# Brain1portB.net
KiCad netlist of a schematic drawn in EAGLE
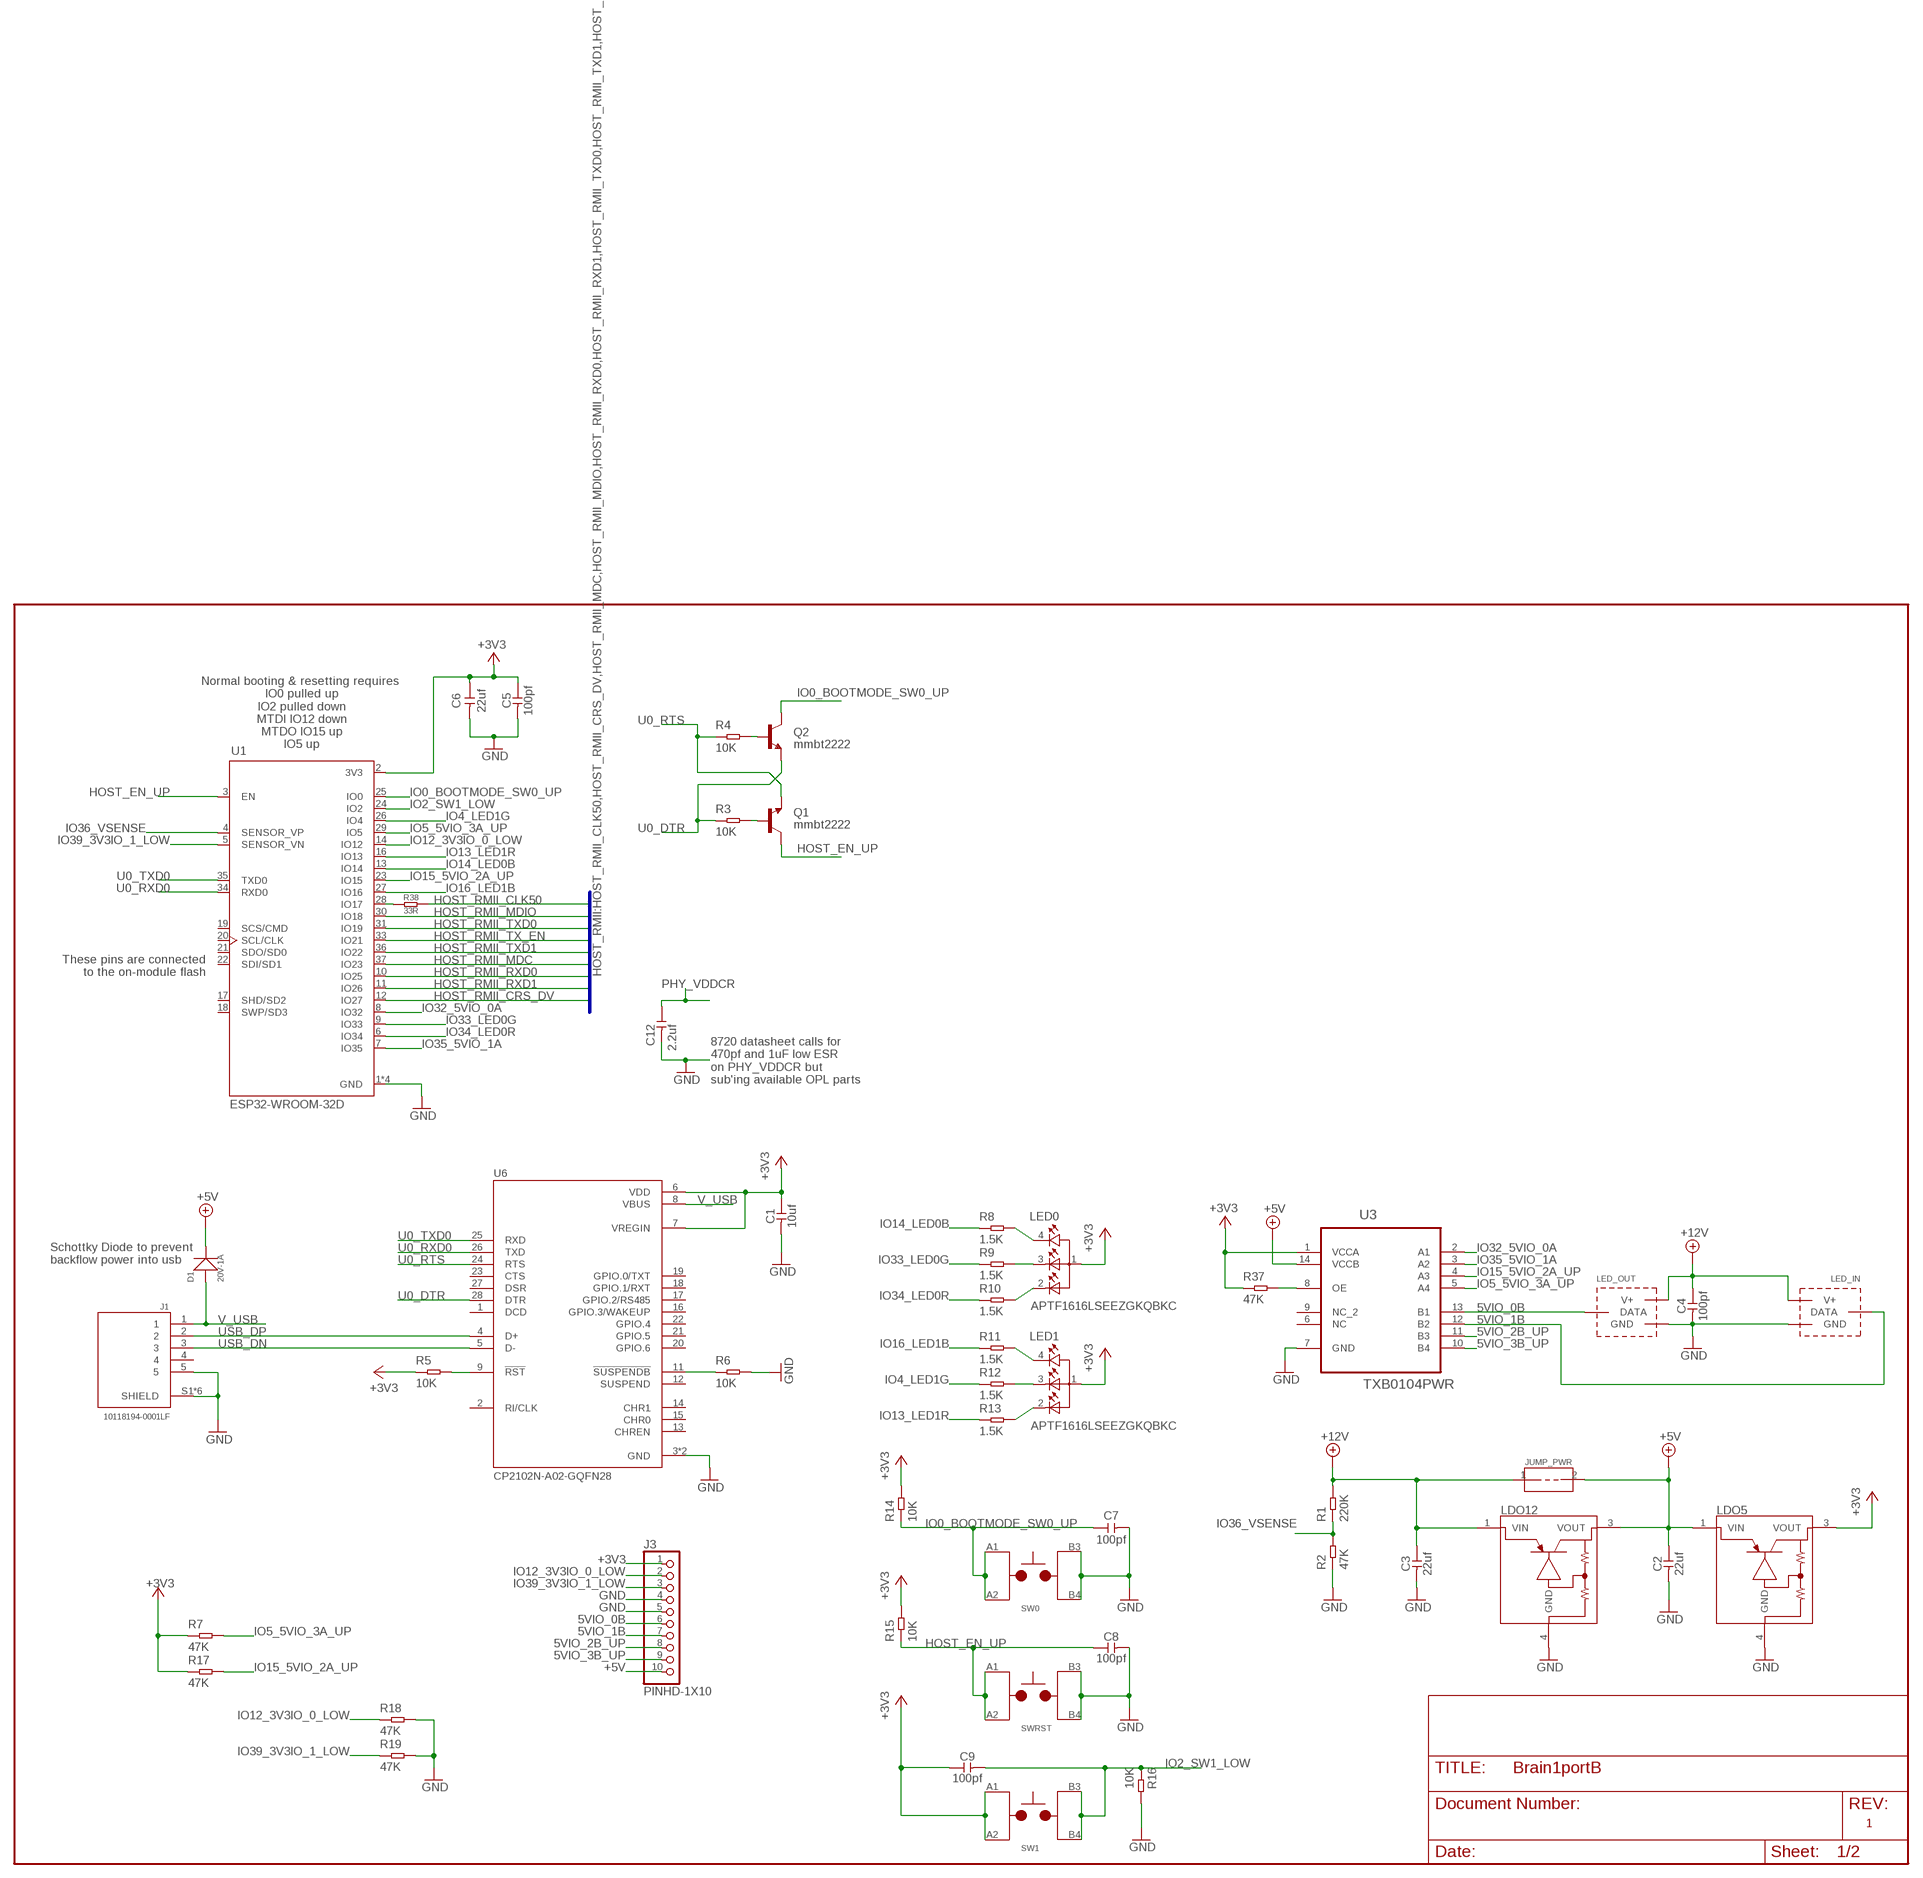
[diagram p0: schematic, sheet 1]
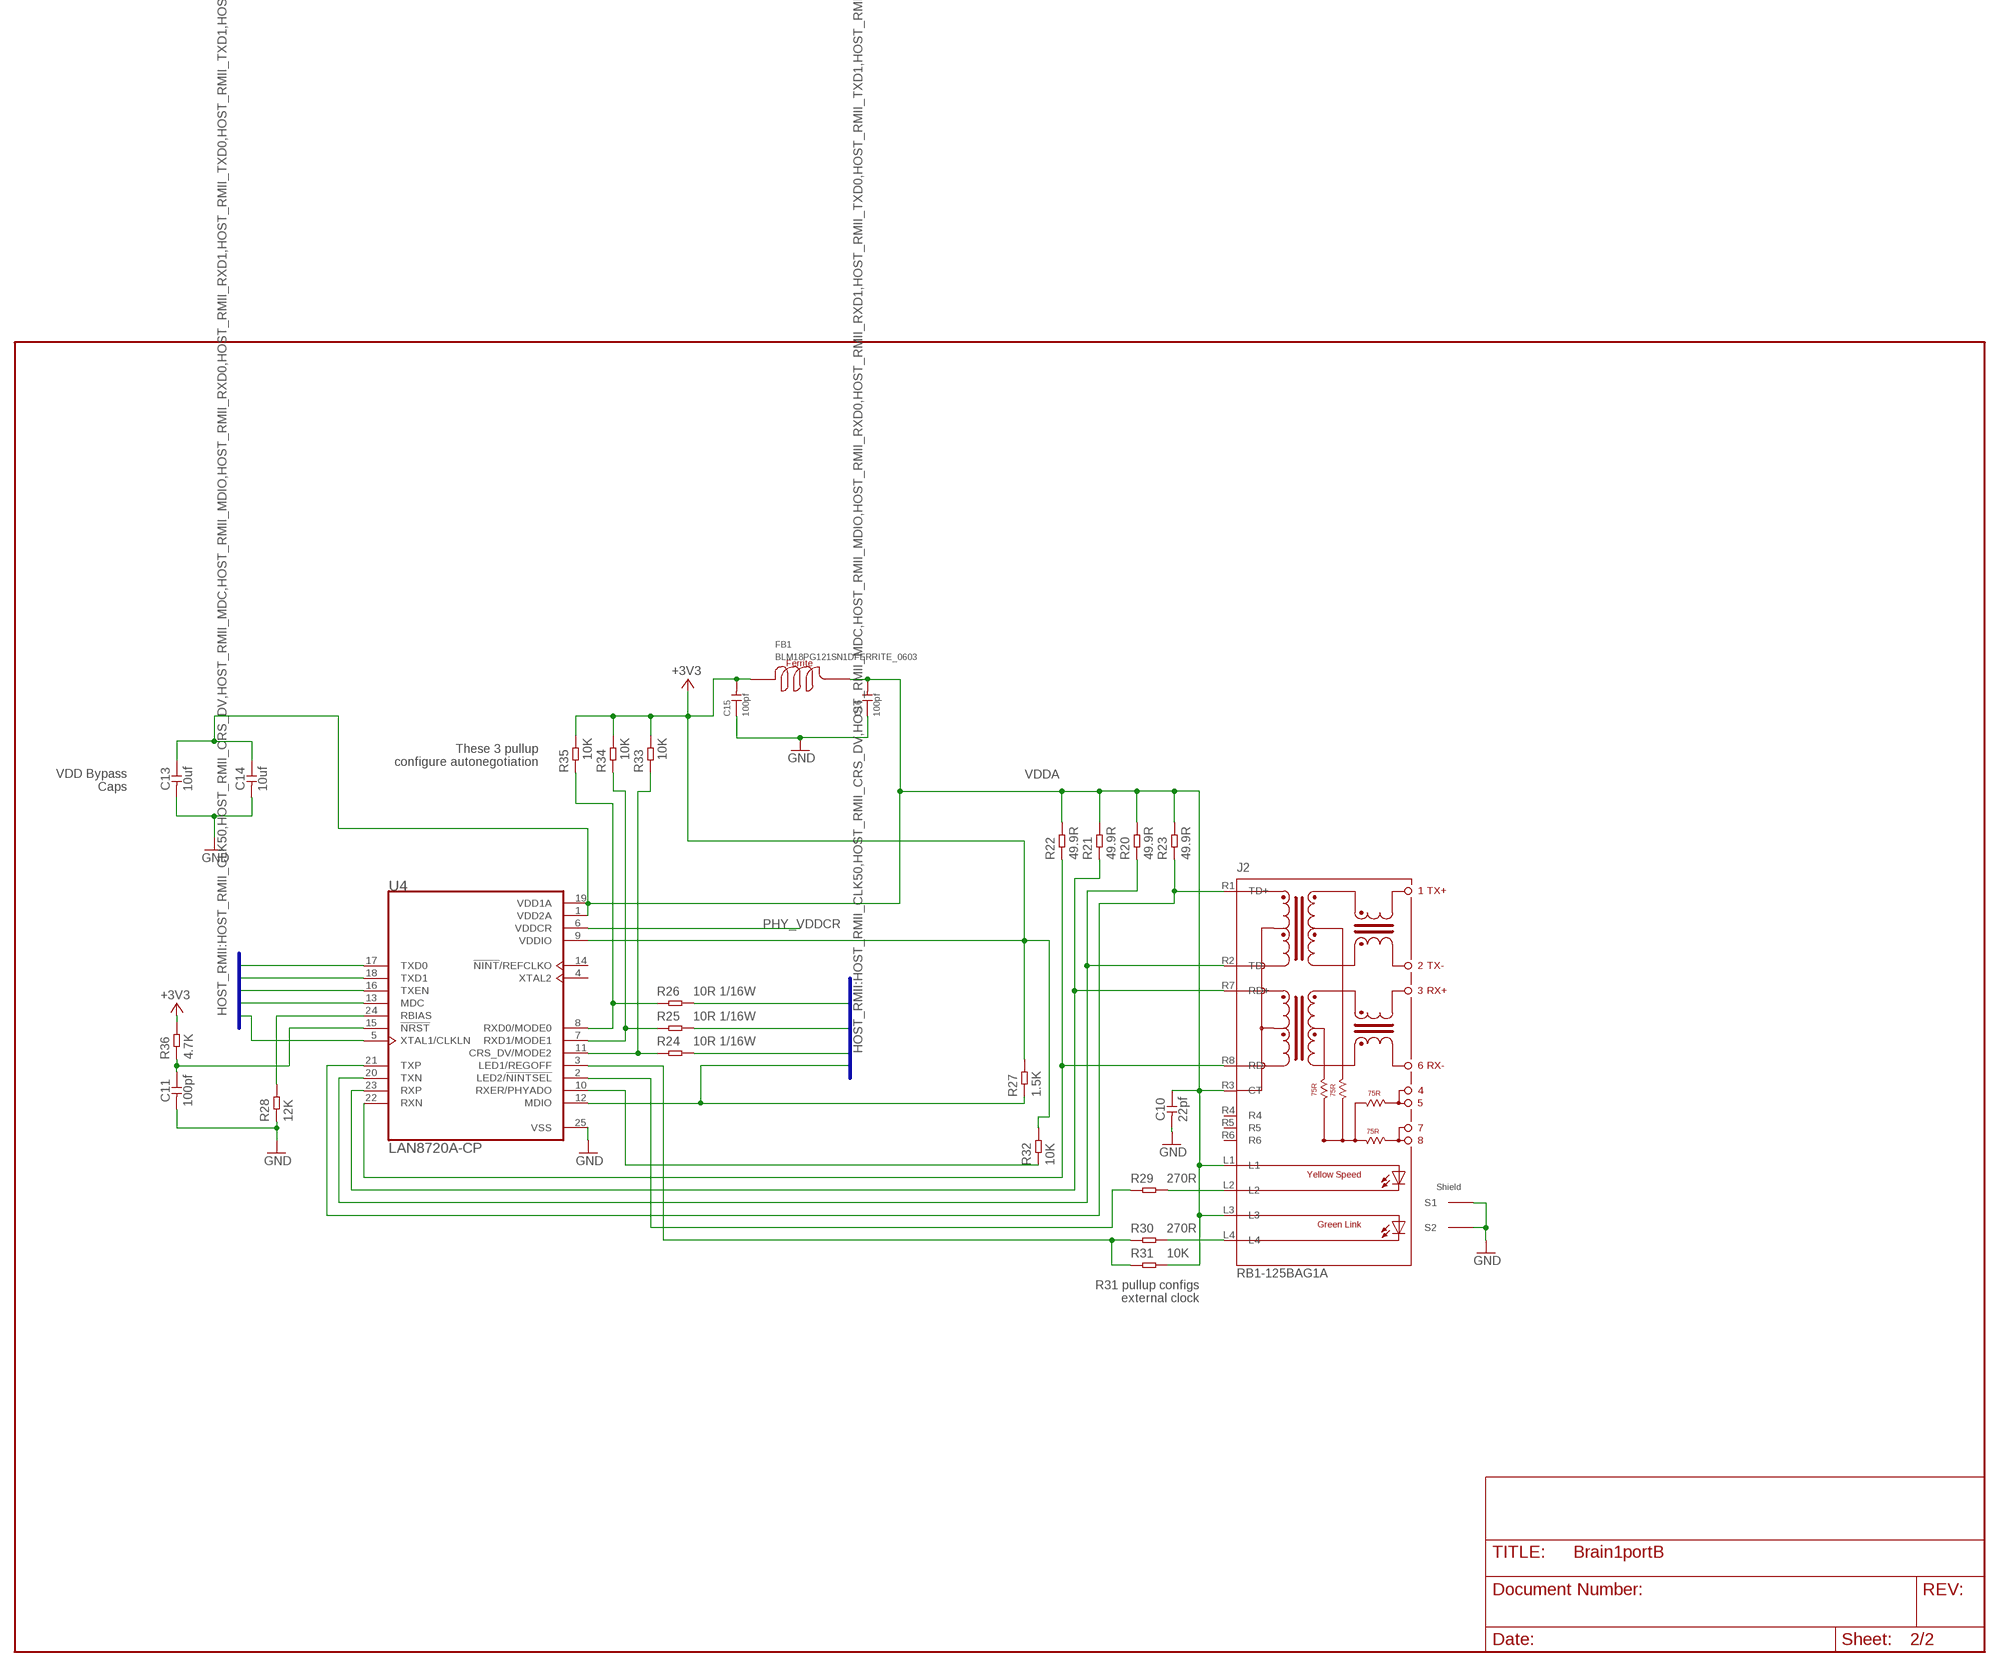
[diagram p1: schematic, sheet 2]

(export (version "E")
  (design (tool "Eeschema 10.0.6"))
  (components
    (comp (ref "C10")
      (value "22pf")
      (footprint "eagle-import:C0402")
      (fields (field (name "MPN") "CC0402JRNPO9BN220"))
      (libsource (lib "eagle-import") (part "CERAMIC-22PF-50V-5%-NPO(0402)"))
    )
    (comp (ref "C11")
      (value "100pf")
      (footprint "eagle-import:C0402")
      (fields (field (name "MPN") "CC0402JRNPO9BN101"))
      (libsource (lib "eagle-import") (part "CERAMIC-100PF-50V-5%-NPO(0402)"))
    )
    (comp (ref "C13")
      (value "10uf")
      (footprint "eagle-import:C0402")
      (fields (field (name "MPN") "CC0402MRX5R5BB106"))
      (libsource (lib "eagle-import") (part "CERAMIC-10UF-6.3V-20%-X5R(0402)"))
    )
    (comp (ref "C14")
      (value "10uf")
      (footprint "eagle-import:C0402")
      (fields (field (name "MPN") "CC0402MRX5R5BB106"))
      (libsource (lib "eagle-import") (part "CERAMIC-10UF-6.3V-20%-X5R(0402)"))
    )
    (comp (ref "C15")
      (value "100pf")
      (footprint "eagle-import:C0402")
      (fields (field (name "MPN") "CC0402JRNPO9BN101"))
      (libsource (lib "eagle-import") (part "CERAMIC-100PF-50V-5%-NPO(0402)"))
    )
    (comp (ref "C16")
      (value "100pf")
      (footprint "eagle-import:C0402")
      (fields (field (name "MPN") "CC0402JRNPO9BN101"))
      (libsource (lib "eagle-import") (part "CERAMIC-100PF-50V-5%-NPO(0402)"))
    )
    (comp (ref "FB1")
      (value "BLM18PG121SN1DFERRITE_0603")
      (footprint "eagle-import:L0603")
      (libsource (lib "eagle-import") (part "BLM18PG121SN1DFERRITE_0603"))
    )
    (comp (ref "J2")
      (value "RB1-125BAG1A")
      (footprint "eagle-import:WIZNET_RB1-125BAG1A")
      (libsource (lib "eagle-import") (part "RB1-125BAG1A"))
    )
    (comp (ref "R20")
      (value "49.9R")
      (footprint "eagle-import:R0402")
      (fields (field (name "MPN") "RC0402FR-0749R9L"))
      (libsource (lib "eagle-import") (part "SMD-RES-49.9R-1%-1/16W(0402)"))
    )
    (comp (ref "R21")
      (value "49.9R")
      (footprint "eagle-import:R0402")
      (fields (field (name "MPN") "RC0402FR-0749R9L"))
      (libsource (lib "eagle-import") (part "SMD-RES-49.9R-1%-1/16W(0402)"))
    )
    (comp (ref "R22")
      (value "49.9R")
      (footprint "eagle-import:R0402")
      (fields (field (name "MPN") "RC0402FR-0749R9L"))
      (libsource (lib "eagle-import") (part "SMD-RES-49.9R-1%-1/16W(0402)"))
    )
    (comp (ref "R23")
      (value "49.9R")
      (footprint "eagle-import:R0402")
      (fields (field (name "MPN") "RC0402FR-0749R9L"))
      (libsource (lib "eagle-import") (part "SMD-RES-49.9R-1%-1/16W(0402)"))
    )
    (comp (ref "R24")
      (value "10R 1/16W")
      (footprint "eagle-import:R0402")
      (fields (field (name "MPN") "RC0402JR-0710RL"))
      (libsource (lib "eagle-import") (part "SMD-RES-10R-5%-1/16W(0402)"))
    )
    (comp (ref "R25")
      (value "10R 1/16W")
      (footprint "eagle-import:R0402")
      (fields (field (name "MPN") "RC0402JR-0710RL"))
      (libsource (lib "eagle-import") (part "SMD-RES-10R-5%-1/16W(0402)"))
    )
    (comp (ref "R26")
      (value "10R 1/16W")
      (footprint "eagle-import:R0402")
      (fields (field (name "MPN") "RC0402JR-0710RL"))
      (libsource (lib "eagle-import") (part "SMD-RES-10R-5%-1/16W(0402)"))
    )
    (comp (ref "R27")
      (value "1.5K")
      (footprint "eagle-import:R0402")
      (fields (field (name "MPN") "RC0402JR-071K5L"))
      (libsource (lib "eagle-import") (part "SMD-RES-1.5K-5%-1/16W(0402)"))
    )
    (comp (ref "R28")
      (value "12K")
      (footprint "eagle-import:R0402")
      (fields (field (name "MPN") "RC0402JR-070RL"))
      (libsource (lib "eagle-import") (part "SMD-RES-12K-1%-1/16W(0402)"))
    )
    (comp (ref "R29")
      (value "270R")
      (footprint "eagle-import:R0402")
      (fields (field (name "MPN") "RC0402JR-070RL"))
      (libsource (lib "eagle-import") (part "SMD-RES-270R-1%-1/16W(0402)"))
    )
    (comp (ref "R30")
      (value "270R")
      (footprint "eagle-import:R0402")
      (fields (field (name "MPN") "RC0402JR-070RL"))
      (libsource (lib "eagle-import") (part "SMD-RES-270R-1%-1/16W(0402)"))
    )
    (comp (ref "R31")
      (value "10K")
      (footprint "eagle-import:R0402")
      (fields (field (name "MPN") "RC0402JR-0710KL"))
      (libsource (lib "eagle-import") (part "SMD-RES-10K-5%-1/(0402)"))
    )
    (comp (ref "R32")
      (value "10K")
      (footprint "eagle-import:R0402")
      (fields (field (name "MPN") "RC0402JR-0710KL"))
      (libsource (lib "eagle-import") (part "SMD-RES-10K-5%-1/(0402)"))
    )
    (comp (ref "R33")
      (value "10K")
      (footprint "eagle-import:R0402")
      (fields (field (name "MPN") "RC0402JR-0710KL"))
      (libsource (lib "eagle-import") (part "SMD-RES-10K-5%-1/(0402)"))
    )
    (comp (ref "R34")
      (value "10K")
      (footprint "eagle-import:R0402")
      (fields (field (name "MPN") "RC0402JR-0710KL"))
      (libsource (lib "eagle-import") (part "SMD-RES-10K-5%-1/(0402)"))
    )
    (comp (ref "R35")
      (value "10K")
      (footprint "eagle-import:R0402")
      (fields (field (name "MPN") "RC0402JR-0710KL"))
      (libsource (lib "eagle-import") (part "SMD-RES-10K-5%-1/(0402)"))
    )
    (comp (ref "R36")
      (value "4.7K")
      (footprint "eagle-import:R0402")
      (fields (field (name "MPN") "RC0402JR-074K7L"))
      (libsource (lib "eagle-import") (part "SMD-RES-4.7K-5%-1/16W(0402)"))
    )
    (comp (ref "U4")
      (value "LAN8720A-CP")
      (footprint "eagle-import:QFN50P400X400X100-25N")
      (fields (field (name "DIGI-KEY_PART_NUMBER") "638-1080-ND") (field (name "MF") "Microchip"))
      (libsource (lib "eagle-import") (part "LAN8720A-CP"))
    )
    (comp (ref "C1")
      (value "10uf")
      (footprint "eagle-import:C0402")
      (fields (field (name "MPN") "CC0402MRX5R5BB106"))
      (libsource (lib "eagle-import") (part "CERAMIC-10UF-6.3V-20%-X5R(0402)"))
    )
    (comp (ref "C2")
      (value "22uf")
      (footprint "eagle-import:C0805")
      (fields (field (name "MPN") "CC0805MKX5R5BB226"))
      (libsource (lib "eagle-import") (part "CERAMIC-22UF-6.3V-20%-X5R(0805)"))
    )
    (comp (ref "C3")
      (value "22uf")
      (footprint "eagle-import:C0805")
      (fields (field (name "MPN") "CC0805MKX5R5BB226"))
      (libsource (lib "eagle-import") (part "CERAMIC-22UF-6.3V-20%-X5R(0805)"))
    )
    (comp (ref "C4")
      (value "100pf")
      (footprint "eagle-import:C0402")
      (fields (field (name "MPN") "CC0402JRNPO9BN101"))
      (libsource (lib "eagle-import") (part "CERAMIC-100PF-50V-5%-NPO(0402)"))
    )
    (comp (ref "C5")
      (value "100pf")
      (footprint "eagle-import:C0402")
      (fields (field (name "MPN") "CC0402JRNPO9BN101"))
      (libsource (lib "eagle-import") (part "CERAMIC-100PF-50V-5%-NPO(0402)"))
    )
    (comp (ref "C6")
      (value "22uf")
      (footprint "eagle-import:C0805")
      (fields (field (name "MPN") "CC0805MKX5R5BB226"))
      (libsource (lib "eagle-import") (part "CERAMIC-22UF-6.3V-20%-X5R(0805)"))
    )
    (comp (ref "C7")
      (value "100pf")
      (footprint "eagle-import:C0402")
      (fields (field (name "MPN") "CC0402JRNPO9BN101"))
      (libsource (lib "eagle-import") (part "CERAMIC-100PF-50V-5%-NPO(0402)"))
    )
    (comp (ref "C8")
      (value "100pf")
      (footprint "eagle-import:C0402")
      (fields (field (name "MPN") "CC0402JRNPO9BN101"))
      (libsource (lib "eagle-import") (part "CERAMIC-100PF-50V-5%-NPO(0402)"))
    )
    (comp (ref "C9")
      (value "100pf")
      (footprint "eagle-import:C0402")
      (fields (field (name "MPN") "CC0402JRNPO9BN101"))
      (libsource (lib "eagle-import") (part "CERAMIC-100PF-50V-5%-NPO(0402)"))
    )
    (comp (ref "C12")
      (value "2.2uf")
      (footprint "eagle-import:C0603")
      (fields (field (name "MPN") "CC0603KRX7R6BB225"))
      (libsource (lib "eagle-import") (part "CERAMIC-2.2UF-10V-10%-X7R(0603)"))
    )
    (comp (ref "D1")
      (value "20V-1A")
      (footprint "eagle-import:SOD-123")
      (fields (field (name "MPN") "B5819W"))
      (libsource (lib "eagle-import") (part "SMD-DIODE-SCHOTTKY-20V-1A(SOD-123)"))
    )
    (comp (ref "J1")
      (value "10118194-0001LF")
      (footprint "eagle-import:AMPHENOL_10118194-0001LF")
      (fields (field (name "DIGI-KEY_PART_NUMBER") "609-4618-1-ND") (field (name "MF") "Amphenol ICC"))
      (libsource (lib "eagle-import") (part "10118194-0001LF"))
    )
    (comp (ref "J3")
      (value "PINHD-1X10")
      (footprint "eagle-import:1X10-BIG")
      (libsource (lib "eagle-import") (part "PINHD-1X10"))
    )
    (comp (ref "JUMP_PWR")
      (value "PWR_SUPPLY_SHORT050_DRILLED")
      (footprint "eagle-import:SHORT_050_DRILLED")
      (libsource (lib "eagle-import") (part "PWR_SUPPLY_SHORT050_DRILLED"))
    )
    (comp (ref "LDO5")
      (value "NCP5501DPAK3")
      (footprint "eagle-import:TO229P990X238-3")
      (libsource (lib "eagle-import") (part "NCP5501DPAK3"))
    )
    (comp (ref "LDO12")
      (value "NCP5501DPAK3")
      (footprint "eagle-import:TO229P990X238-3")
      (libsource (lib "eagle-import") (part "NCP5501DPAK3"))
    )
    (comp (ref "LED0")
      (value "APTF1616LSEEZGKQBKC")
      (footprint "eagle-import:LEDSC160X160X070-4N")
      (fields (field (name "MF") "Kingbright"))
      (libsource (lib "eagle-import") (part "APTF1616LSEEZGKQBKC"))
    )
    (comp (ref "LED1")
      (value "APTF1616LSEEZGKQBKC")
      (footprint "eagle-import:LEDSC160X160X070-4N")
      (fields (field (name "MF") "Kingbright"))
      (libsource (lib "eagle-import") (part "APTF1616LSEEZGKQBKC"))
    )
    (comp (ref "LED_IN")
      (value "3WAY_LED_CONWIRES")
      (footprint "eagle-import:3WAY_LED_WIRES")
      (libsource (lib "eagle-import") (part "3WAY_LED_CONWIRES"))
    )
    (comp (ref "LED_OUT")
      (value "3WAY_LED_CONWIRES")
      (footprint "eagle-import:3WAY_LED_WIRES")
      (libsource (lib "eagle-import") (part "3WAY_LED_CONWIRES"))
    )
    (comp (ref "Q1")
      (value "mmbt2222")
      (footprint "eagle-import:SOT23-BEC")
      (libsource (lib "eagle-import") (part "-NPN-SOT23-BECMMBT2222ALT1"))
    )
    (comp (ref "Q2")
      (value "mmbt2222")
      (footprint "eagle-import:SOT23-BEC")
      (libsource (lib "eagle-import") (part "-NPN-SOT23-BECMMBT2222ALT1"))
    )
    (comp (ref "R1")
      (value "220K")
      (footprint "eagle-import:R0402")
      (fields (field (name "MPN") "RC0402JR-070RL"))
      (libsource (lib "eagle-import") (part "SMD-RES-220K-5%-1/16W(0402)"))
    )
    (comp (ref "R2")
      (value "47K")
      (footprint "eagle-import:R0402")
      (fields (field (name "MPN") "RC0402JR-0747KL"))
      (libsource (lib "eagle-import") (part "SMD-RES-47K-5%-1/16W(0402)"))
    )
    (comp (ref "R3")
      (value "10K")
      (footprint "eagle-import:R0402")
      (fields (field (name "MPN") "RC0402JR-0710KL"))
      (libsource (lib "eagle-import") (part "SMD-RES-10K-5%-1/(0402)"))
    )
    (comp (ref "R4")
      (value "10K")
      (footprint "eagle-import:R0402")
      (fields (field (name "MPN") "RC0402JR-0710KL"))
      (libsource (lib "eagle-import") (part "SMD-RES-10K-5%-1/(0402)"))
    )
    (comp (ref "R5")
      (value "10K")
      (footprint "eagle-import:R0402")
      (fields (field (name "MPN") "RC0402JR-0710KL"))
      (libsource (lib "eagle-import") (part "SMD-RES-10K-5%-1/(0402)"))
    )
    (comp (ref "R6")
      (value "10K")
      (footprint "eagle-import:R0402")
      (fields (field (name "MPN") "RC0402JR-0710KL"))
      (libsource (lib "eagle-import") (part "SMD-RES-10K-5%-1/(0402)"))
    )
    (comp (ref "R7")
      (value "47K")
      (footprint "eagle-import:R0402")
      (fields (field (name "MPN") "RC0402JR-0747KL"))
      (libsource (lib "eagle-import") (part "SMD-RES-47K-5%-1/16W(0402)"))
    )
    (comp (ref "R8")
      (value "1.5K")
      (footprint "eagle-import:R0402")
      (fields (field (name "MPN") "RC0402JR-071K5L"))
      (libsource (lib "eagle-import") (part "SMD-RES-1.5K-5%-1/16W(0402)"))
    )
    (comp (ref "R9")
      (value "1.5K")
      (footprint "eagle-import:R0402")
      (fields (field (name "MPN") "RC0402JR-071K5L"))
      (libsource (lib "eagle-import") (part "SMD-RES-1.5K-5%-1/16W(0402)"))
    )
    (comp (ref "R10")
      (value "1.5K")
      (footprint "eagle-import:R0402")
      (fields (field (name "MPN") "RC0402JR-071K5L"))
      (libsource (lib "eagle-import") (part "SMD-RES-1.5K-5%-1/16W(0402)"))
    )
    (comp (ref "R11")
      (value "1.5K")
      (footprint "eagle-import:R0402")
      (fields (field (name "MPN") "RC0402JR-071K5L"))
      (libsource (lib "eagle-import") (part "SMD-RES-1.5K-5%-1/16W(0402)"))
    )
    (comp (ref "R12")
      (value "1.5K")
      (footprint "eagle-import:R0402")
      (fields (field (name "MPN") "RC0402JR-071K5L"))
      (libsource (lib "eagle-import") (part "SMD-RES-1.5K-5%-1/16W(0402)"))
    )
    (comp (ref "R13")
      (value "1.5K")
      (footprint "eagle-import:R0402")
      (fields (field (name "MPN") "RC0402JR-071K5L"))
      (libsource (lib "eagle-import") (part "SMD-RES-1.5K-5%-1/16W(0402)"))
    )
    (comp (ref "R14")
      (value "10K")
      (footprint "eagle-import:R0402")
      (fields (field (name "MPN") "RC0402JR-0710KL"))
      (libsource (lib "eagle-import") (part "SMD-RES-10K-5%-1/(0402)"))
    )
    (comp (ref "R15")
      (value "10K")
      (footprint "eagle-import:R0402")
      (fields (field (name "MPN") "RC0402JR-0710KL"))
      (libsource (lib "eagle-import") (part "SMD-RES-10K-5%-1/(0402)"))
    )
    (comp (ref "R16")
      (value "10K")
      (footprint "eagle-import:R0402")
      (fields (field (name "MPN") "RC0402JR-0710KL"))
      (libsource (lib "eagle-import") (part "SMD-RES-10K-5%-1/(0402)"))
    )
    (comp (ref "R17")
      (value "47K")
      (footprint "eagle-import:R0402")
      (fields (field (name "MPN") "RC0402JR-0747KL"))
      (libsource (lib "eagle-import") (part "SMD-RES-47K-5%-1/16W(0402)"))
    )
    (comp (ref "R18")
      (value "47K")
      (footprint "eagle-import:R0402")
      (fields (field (name "MPN") "RC0402JR-0747KL"))
      (libsource (lib "eagle-import") (part "SMD-RES-47K-5%-1/16W(0402)"))
    )
    (comp (ref "R19")
      (value "47K")
      (footprint "eagle-import:R0402")
      (fields (field (name "MPN") "RC0402JR-0747KL"))
      (libsource (lib "eagle-import") (part "SMD-RES-47K-5%-1/16W(0402)"))
    )
    (comp (ref "R37")
      (value "47K")
      (footprint "eagle-import:R0402")
      (fields (field (name "MPN") "RC0402JR-0747KL"))
      (libsource (lib "eagle-import") (part "SMD-RES-47K-5%-1/16W(0402)"))
    )
    (comp (ref "R38")
      (value "33R")
      (footprint "eagle-import:R0603")
      (fields (field (name "MPN") "RC0603FR-071K5L"))
      (libsource (lib "eagle-import") (part "SMD-RES-33R-5%-1/10W(0603)"))
    )
    (comp (ref "SW0")
      (value "TL3301T3301SWITCH")
      (footprint "eagle-import:SW-4")
      (libsource (lib "eagle-import") (part "TL3301T3301SWITCH"))
    )
    (comp (ref "SW1")
      (value "TL3301T3301SWITCH")
      (footprint "eagle-import:SW-4")
      (libsource (lib "eagle-import") (part "TL3301T3301SWITCH"))
    )
    (comp (ref "SWRST")
      (value "TL3301T3301SWITCH")
      (footprint "eagle-import:SW-4")
      (libsource (lib "eagle-import") (part "TL3301T3301SWITCH"))
    )
    (comp (ref "U1")
      (value "ESP32-WROOM-32D")
      (footprint "eagle-import:MODULE_ESP32-WROOM-32D")
      (fields (field (name "DIGI-KEY_PART_NUMBER") "1904-1023-1-ND") (field (name "MF") "Espressif Systems"))
      (libsource (lib "eagle-import") (part "ESP32-WROOM-32D"))
    )
    (comp (ref "U3")
      (value "TXB0104PWR")
      (footprint "eagle-import:SOP65P640X120-14N")
      (fields (field (name "MF") "Texas Instruments"))
      (libsource (lib "eagle-import") (part "TXB0104PWR"))
    )
    (comp (ref "U6")
      (value "CP2102N-A02-GQFN28")
      (footprint "eagle-import:QFN50P500X500X80-29N")
      (fields (field (name "MF") "Silicon Labs") (field (name "MP") "CP2102N-A01-GQFN28"))
      (libsource (lib "eagle-import") (part "CP2102N-A01-GQFN28"))
    )
  )
  (nets
    (net (code "3") (name "+3V3") (class "Default")
      (node (ref "C1") (pin "1") (pinfunction "1_1") (pintype "passive"))
      (node (ref "C15") (pin "2") (pinfunction "2_2") (pintype "passive"))
      (node (ref "C5") (pin "1") (pinfunction "1_1") (pintype "passive"))
      (node (ref "C6") (pin "1") (pinfunction "1_1") (pintype "passive"))
      (node (ref "C9") (pin "1") (pinfunction "1_1") (pintype "passive"))
      (node (ref "FB1") (pin "1") (pinfunction "P$1_1") (pintype "bidirectional"))
      (node (ref "J3") (pin "1") (pinfunction "1_1") (pintype "passive"))
      (node (ref "LDO5") (pin "3") (pinfunction "VOUT_3") (pintype "power_in"))
      (node (ref "LED0") (pin "1") (pinfunction "1_1") (pintype "passive"))
      (node (ref "LED1") (pin "1") (pinfunction "1_1") (pintype "passive"))
      (node (ref "R14") (pin "2") (pinfunction "2_2") (pintype "passive"))
      (node (ref "R15") (pin "2") (pinfunction "2_2") (pintype "passive"))
      (node (ref "R17") (pin "1") (pinfunction "1_1") (pintype "passive"))
      (node (ref "R27") (pin "2") (pinfunction "2_2") (pintype "passive"))
      (node (ref "R32") (pin "2") (pinfunction "2_2") (pintype "passive"))
      (node (ref "R33") (pin "2") (pinfunction "2_2") (pintype "passive"))
      (node (ref "R34") (pin "2") (pinfunction "2_2") (pintype "passive"))
      (node (ref "R35") (pin "2") (pinfunction "2_2") (pintype "passive"))
      (node (ref "R36") (pin "2") (pinfunction "2_2") (pintype "passive"))
      (node (ref "R37") (pin "1") (pinfunction "1_1") (pintype "passive"))
      (node (ref "R5") (pin "1") (pinfunction "1_1") (pintype "passive"))
      (node (ref "R7") (pin "1") (pinfunction "1_1") (pintype "passive"))
      (node (ref "SW1") (pin "A1") (pinfunction "1_A1") (pintype "bidirectional"))
      (node (ref "SW1") (pin "A2") (pinfunction "2_A2") (pintype "bidirectional"))
      (node (ref "U1") (pin "2") (pinfunction "3V3_2") (pintype "power_in"))
      (node (ref "U3") (pin "1") (pinfunction "VCCA_1") (pintype "power_in"))
      (node (ref "U4") (pin "9") (pinfunction "VDDIO_9") (pintype "power_in"))
      (node (ref "U6") (pin "6") (pinfunction "VDD_6") (pintype "power_in"))
      (node (ref "U6") (pin "7") (pinfunction "VREGIN_7") (pintype "power_in"))
    )
    (net (code "4") (name "+5V") (class "Default")
      (node (ref "C2") (pin "1") (pinfunction "1_1") (pintype "passive"))
      (node (ref "D1") (pin "-") (pinfunction "-_-") (pintype "passive"))
      (node (ref "J3") (pin "10") (pinfunction "10_10") (pintype "passive"))
      (node (ref "JUMP_PWR") (pin "2") (pinfunction "P$2_2") (pintype "bidirectional"))
      (node (ref "LDO12") (pin "3") (pinfunction "VOUT_3") (pintype "power_in"))
      (node (ref "LDO5") (pin "1") (pinfunction "VIN_1") (pintype "power_in"))
      (node (ref "U3") (pin "14") (pinfunction "VCCB_14") (pintype "power_in"))
    )
    (net (code "5") (name "+12V") (class "Default")
      (node (ref "C3") (pin "1") (pinfunction "1_1") (pintype "passive"))
      (node (ref "C4") (pin "1") (pinfunction "1_1") (pintype "passive"))
      (node (ref "JUMP_PWR") (pin "1") (pinfunction "P$1_1") (pintype "bidirectional"))
      (node (ref "LDO12") (pin "1") (pinfunction "VIN_1") (pintype "power_in"))
      (node (ref "LED_IN") (pin "V+") (pinfunction "V+_V+") (pintype "power_in"))
      (node (ref "LED_OUT") (pin "V+") (pinfunction "V+_V+") (pintype "power_in"))
      (node (ref "R1") (pin "2") (pinfunction "2_2") (pintype "passive"))
    )
    (net (code "8") (name "5VIO_0B") (class "Default")
      (node (ref "J3") (pin "6") (pinfunction "6_6") (pintype "passive"))
      (node (ref "LED_OUT") (pin "DATA") (pinfunction "DATA_DATA") (pintype "bidirectional"))
      (node (ref "U3") (pin "13") (pinfunction "B1_13") (pintype "bidirectional"))
    )
    (net (code "9") (name "5VIO_1B") (class "Default")
      (node (ref "J3") (pin "7") (pinfunction "7_7") (pintype "passive"))
      (node (ref "LED_IN") (pin "DATA") (pinfunction "DATA_DATA") (pintype "bidirectional"))
      (node (ref "U3") (pin "12") (pinfunction "B2_12") (pintype "bidirectional"))
    )
    (net (code "10") (name "5VIO_2B_UP") (class "Default")
      (node (ref "J3") (pin "8") (pinfunction "8_8") (pintype "passive"))
      (node (ref "U3") (pin "11") (pinfunction "B3_11") (pintype "bidirectional"))
    )
    (net (code "11") (name "5VIO_3B_UP") (class "Default")
      (node (ref "J3") (pin "9") (pinfunction "9_9") (pintype "passive"))
      (node (ref "U3") (pin "10") (pinfunction "B4_10") (pintype "bidirectional"))
    )
    (net (code "12") (name "GND") (class "Default")
      (node (ref "C1") (pin "2") (pinfunction "2_2") (pintype "passive"))
      (node (ref "C10") (pin "2") (pinfunction "2_2") (pintype "passive"))
      (node (ref "C11") (pin "2") (pinfunction "2_2") (pintype "passive"))
      (node (ref "C12") (pin "2") (pinfunction "2_2") (pintype "passive"))
      (node (ref "C13") (pin "2") (pinfunction "2_2") (pintype "passive"))
      (node (ref "C14") (pin "2") (pinfunction "2_2") (pintype "passive"))
      (node (ref "C15") (pin "1") (pinfunction "1_1") (pintype "passive"))
      (node (ref "C16") (pin "1") (pinfunction "1_1") (pintype "passive"))
      (node (ref "C2") (pin "2") (pinfunction "2_2") (pintype "passive"))
      (node (ref "C3") (pin "2") (pinfunction "2_2") (pintype "passive"))
      (node (ref "C4") (pin "2") (pinfunction "2_2") (pintype "passive"))
      (node (ref "C5") (pin "2") (pinfunction "2_2") (pintype "passive"))
      (node (ref "C6") (pin "2") (pinfunction "2_2") (pintype "passive"))
      (node (ref "C7") (pin "2") (pinfunction "2_2") (pintype "passive"))
      (node (ref "C8") (pin "2") (pinfunction "2_2") (pintype "passive"))
      (node (ref "J1") (pin "5") (pinfunction "5_5") (pintype "passive"))
      (node (ref "J1") (pin "S1") (pinfunction "SHIELD_S1") (pintype "passive"))
      (node (ref "J1") (pin "S2") (pinfunction "SHIELD_S2") (pintype "passive"))
      (node (ref "J1") (pin "S3") (pinfunction "SHIELD_S3") (pintype "passive"))
      (node (ref "J1") (pin "S4") (pinfunction "SHIELD_S4") (pintype "passive"))
      (node (ref "J1") (pin "S5") (pinfunction "SHIELD_S5") (pintype "passive"))
      (node (ref "J1") (pin "S6") (pinfunction "SHIELD_S6") (pintype "passive"))
      (node (ref "J2") (pin "S1") (pinfunction "S1_S1") (pintype "power_in"))
      (node (ref "J2") (pin "S2") (pinfunction "S2_S2") (pintype "power_in"))
      (node (ref "J3") (pin "4") (pinfunction "4_4") (pintype "passive"))
      (node (ref "J3") (pin "5") (pinfunction "5_5") (pintype "passive"))
      (node (ref "LDO12") (pin "4") (pinfunction "GND_4") (pintype "power_in"))
      (node (ref "LDO5") (pin "4") (pinfunction "GND_4") (pintype "power_in"))
      (node (ref "LED_IN") (pin "GND") (pinfunction "GND_GND") (pintype "power_in"))
      (node (ref "LED_OUT") (pin "GND") (pinfunction "GND_GND") (pintype "power_in"))
      (node (ref "R16") (pin "2") (pinfunction "2_2") (pintype "passive"))
      (node (ref "R18") (pin "2") (pinfunction "2_2") (pintype "passive"))
      (node (ref "R19") (pin "2") (pinfunction "2_2") (pintype "passive"))
      (node (ref "R2") (pin "1") (pinfunction "1_1") (pintype "passive"))
      (node (ref "R28") (pin "1") (pinfunction "1_1") (pintype "passive"))
      (node (ref "R6") (pin "2") (pinfunction "2_2") (pintype "passive"))
      (node (ref "SW0") (pin "B3") (pinfunction "3_B3") (pintype "bidirectional"))
      (node (ref "SW0") (pin "B4") (pinfunction "4_B4") (pintype "bidirectional"))
      (node (ref "SWRST") (pin "B3") (pinfunction "3_B3") (pintype "bidirectional"))
      (node (ref "SWRST") (pin "B4") (pinfunction "4_B4") (pintype "bidirectional"))
      (node (ref "U1") (pin "1") (pinfunction "GND_1") (pintype "power_in"))
      (node (ref "U1") (pin "15") (pinfunction "GND_15") (pintype "power_in"))
      (node (ref "U1") (pin "38") (pinfunction "GND_38") (pintype "power_in"))
      (node (ref "U1") (pin "39") (pinfunction "GND_39") (pintype "power_in"))
      (node (ref "U3") (pin "7") (pinfunction "GND_7") (pintype "passive"))
      (node (ref "U4") (pin "25") (pinfunction "VSS_25") (pintype "power_in"))
      (node (ref "U6") (pin "29") (pinfunction "GND_29") (pintype "power_in"))
      (node (ref "U6") (pin "3") (pinfunction "GND_3") (pintype "power_in"))
    )
    (net (code "13") (name "HOST_EN_UP") (class "Default")
      (node (ref "C8") (pin "1") (pinfunction "1_1") (pintype "passive"))
      (node (ref "Q1") (pin "C") (pinfunction "C_C") (pintype "passive"))
      (node (ref "R15") (pin "1") (pinfunction "1_1") (pintype "passive"))
      (node (ref "SWRST") (pin "A1") (pinfunction "1_A1") (pintype "bidirectional"))
      (node (ref "SWRST") (pin "A2") (pinfunction "2_A2") (pintype "bidirectional"))
      (node (ref "U1") (pin "3") (pinfunction "EN_3") (pintype "input"))
    )
    (net (code "14") (name "HOST_RMII_CLK50") (class "Default")
      (node (ref "R38") (pin "2") (pinfunction "2_2") (pintype "passive"))
      (node (ref "U4") (pin "5") (pinfunction "XTAL1/CLKLN_5") (pintype "input"))
    )
    (net (code "15") (name "HOST_RMII_CRS_DV") (class "Default")
      (node (ref "R24") (pin "2") (pinfunction "2_2") (pintype "passive"))
      (node (ref "U1") (pin "12") (pinfunction "IO27_12") (pintype "bidirectional"))
    )
    (net (code "16") (name "HOST_RMII_MDC") (class "Default")
      (node (ref "U1") (pin "37") (pinfunction "IO23_37") (pintype "bidirectional"))
      (node (ref "U4") (pin "13") (pinfunction "MDC_13") (pintype "input"))
    )
    (net (code "17") (name "HOST_RMII_MDIO") (class "Default")
      (node (ref "R27") (pin "1") (pinfunction "1_1") (pintype "passive"))
      (node (ref "U1") (pin "30") (pinfunction "IO18_30") (pintype "bidirectional"))
      (node (ref "U4") (pin "12") (pinfunction "MDIO_12") (pintype "bidirectional"))
    )
    (net (code "18") (name "HOST_RMII_RXD0") (class "Default")
      (node (ref "R26") (pin "2") (pinfunction "2_2") (pintype "passive"))
      (node (ref "U1") (pin "10") (pinfunction "IO25_10") (pintype "bidirectional"))
    )
    (net (code "19") (name "HOST_RMII_RXD1") (class "Default")
      (node (ref "R25") (pin "2") (pinfunction "2_2") (pintype "passive"))
      (node (ref "U1") (pin "11") (pinfunction "IO26_11") (pintype "bidirectional"))
    )
    (net (code "20") (name "HOST_RMII_TXD0") (class "Default")
      (node (ref "U1") (pin "31") (pinfunction "IO19_31") (pintype "bidirectional"))
      (node (ref "U4") (pin "17") (pinfunction "TXD0_17") (pintype "input"))
    )
    (net (code "21") (name "HOST_RMII_TXD1") (class "Default")
      (node (ref "U1") (pin "36") (pinfunction "IO22_36") (pintype "bidirectional"))
      (node (ref "U4") (pin "18") (pinfunction "TXD1_18") (pintype "input"))
    )
    (net (code "22") (name "HOST_RMII_TX_EN") (class "Default")
      (node (ref "U1") (pin "33") (pinfunction "IO21_33") (pintype "bidirectional"))
      (node (ref "U4") (pin "16") (pinfunction "TXEN_16") (pintype "input"))
    )
    (net (code "23") (name "IO0_BOOTMODE_SW0_UP") (class "Default")
      (node (ref "C7") (pin "1") (pinfunction "1_1") (pintype "passive"))
      (node (ref "Q2") (pin "C") (pinfunction "C_C") (pintype "passive"))
      (node (ref "R14") (pin "1") (pinfunction "1_1") (pintype "passive"))
      (node (ref "SW0") (pin "A1") (pinfunction "1_A1") (pintype "bidirectional"))
      (node (ref "SW0") (pin "A2") (pinfunction "2_A2") (pintype "bidirectional"))
      (node (ref "U1") (pin "25") (pinfunction "IO0_25") (pintype "bidirectional"))
    )
    (net (code "24") (name "IO2_SW1_LOW") (class "Default")
      (node (ref "C9") (pin "2") (pinfunction "2_2") (pintype "passive"))
      (node (ref "R16") (pin "1") (pinfunction "1_1") (pintype "passive"))
      (node (ref "SW1") (pin "B3") (pinfunction "3_B3") (pintype "bidirectional"))
      (node (ref "SW1") (pin "B4") (pinfunction "4_B4") (pintype "bidirectional"))
      (node (ref "U1") (pin "24") (pinfunction "IO2_24") (pintype "bidirectional"))
    )
    (net (code "25") (name "IO4_LED1G") (class "Default")
      (node (ref "R12") (pin "1") (pinfunction "1_1") (pintype "passive"))
      (node (ref "U1") (pin "26") (pinfunction "IO4_26") (pintype "bidirectional"))
    )
    (net (code "26") (name "IO5_5VIO_3A_UP") (class "Default")
      (node (ref "R7") (pin "2") (pinfunction "2_2") (pintype "passive"))
      (node (ref "U1") (pin "29") (pinfunction "IO5_29") (pintype "bidirectional"))
      (node (ref "U3") (pin "5") (pinfunction "A4_5") (pintype "bidirectional"))
    )
    (net (code "27") (name "IO12_3V3IO_0_LOW") (class "Default")
      (node (ref "J3") (pin "2") (pinfunction "2_2") (pintype "passive"))
      (node (ref "R18") (pin "1") (pinfunction "1_1") (pintype "passive"))
      (node (ref "U1") (pin "14") (pinfunction "IO12_14") (pintype "bidirectional"))
    )
    (net (code "28") (name "IO13_LED1R") (class "Default")
      (node (ref "R13") (pin "1") (pinfunction "1_1") (pintype "passive"))
      (node (ref "U1") (pin "16") (pinfunction "IO13_16") (pintype "bidirectional"))
    )
    (net (code "29") (name "IO14_LED0B") (class "Default")
      (node (ref "R8") (pin "1") (pinfunction "1_1") (pintype "passive"))
      (node (ref "U1") (pin "13") (pinfunction "IO14_13") (pintype "bidirectional"))
    )
    (net (code "30") (name "IO15_5VIO_2A_UP") (class "Default")
      (node (ref "R17") (pin "2") (pinfunction "2_2") (pintype "passive"))
      (node (ref "U1") (pin "23") (pinfunction "IO15_23") (pintype "bidirectional"))
      (node (ref "U3") (pin "4") (pinfunction "A3_4") (pintype "bidirectional"))
    )
    (net (code "31") (name "IO16_LED1B") (class "Default")
      (node (ref "R11") (pin "1") (pinfunction "1_1") (pintype "passive"))
      (node (ref "U1") (pin "27") (pinfunction "IO16_27") (pintype "bidirectional"))
    )
    (net (code "32") (name "IO32_5VIO_0A") (class "Default")
      (node (ref "U1") (pin "8") (pinfunction "IO32_8") (pintype "bidirectional"))
      (node (ref "U3") (pin "2") (pinfunction "A1_2") (pintype "bidirectional"))
    )
    (net (code "33") (name "IO33_LED0G") (class "Default")
      (node (ref "R9") (pin "1") (pinfunction "1_1") (pintype "passive"))
      (node (ref "U1") (pin "9") (pinfunction "IO33_9") (pintype "bidirectional"))
    )
    (net (code "34") (name "IO34_LED0R") (class "Default")
      (node (ref "R10") (pin "1") (pinfunction "1_1") (pintype "passive"))
      (node (ref "U1") (pin "6") (pinfunction "IO34_6") (pintype "bidirectional"))
    )
    (net (code "35") (name "IO35_5VIO_1A") (class "Default")
      (node (ref "U1") (pin "7") (pinfunction "IO35_7") (pintype "bidirectional"))
      (node (ref "U3") (pin "3") (pinfunction "A2_3") (pintype "bidirectional"))
    )
    (net (code "36") (name "IO36_VSENSE") (class "Default")
      (node (ref "R1") (pin "1") (pinfunction "1_1") (pintype "passive"))
      (node (ref "R2") (pin "2") (pinfunction "2_2") (pintype "passive"))
      (node (ref "U1") (pin "4") (pinfunction "SENSOR_VP_4") (pintype "input"))
    )
    (net (code "37") (name "IO39_3V3IO_1_LOW") (class "Default")
      (node (ref "J3") (pin "3") (pinfunction "3_3") (pintype "passive"))
      (node (ref "R19") (pin "1") (pinfunction "1_1") (pintype "passive"))
      (node (ref "U1") (pin "5") (pinfunction "SENSOR_VN_5") (pintype "input"))
    )
    (net (code "38") (name "Net-(J2-PadL2)") (class "Default")
      (node (ref "J2") (pin "L2") (pinfunction "L2_L2") (pintype "passive"))
      (node (ref "R29") (pin "2") (pinfunction "2_2") (pintype "passive"))
    )
    (net (code "39") (name "Net-(J2-PadL4)") (class "Default")
      (node (ref "J2") (pin "L4") (pinfunction "L4_L4") (pintype "passive"))
      (node (ref "R30") (pin "2") (pinfunction "2_2") (pintype "passive"))
    )
    (net (code "40") (name "Net-(J2-RD+)") (class "Default")
      (node (ref "J2") (pin "R7") (pinfunction "RD+_R7") (pintype "input"))
      (node (ref "R21") (pin "1") (pinfunction "1_1") (pintype "passive"))
      (node (ref "U4") (pin "23") (pinfunction "RXP_23") (pintype "bidirectional"))
    )
    (net (code "41") (name "Net-(J2-RD-)") (class "Default")
      (node (ref "J2") (pin "R8") (pinfunction "RD-_R8") (pintype "input"))
      (node (ref "R22") (pin "1") (pinfunction "1_1") (pintype "passive"))
      (node (ref "U4") (pin "22") (pinfunction "RXN_22") (pintype "bidirectional"))
    )
    (net (code "42") (name "Net-(J2-TD+)") (class "Default")
      (node (ref "J2") (pin "R1") (pinfunction "TD+_R1") (pintype "input"))
      (node (ref "R23") (pin "1") (pinfunction "1_1") (pintype "passive"))
      (node (ref "U4") (pin "21") (pinfunction "TXP_21") (pintype "bidirectional"))
    )
    (net (code "43") (name "Net-(J2-TD-)") (class "Default")
      (node (ref "J2") (pin "R2") (pinfunction "TD-_R2") (pintype "input"))
      (node (ref "R20") (pin "1") (pinfunction "1_1") (pintype "passive"))
      (node (ref "U4") (pin "20") (pinfunction "TXN_20") (pintype "bidirectional"))
    )
    (net (code "44") (name "Net-(LED0-Pad2)") (class "Default")
      (node (ref "LED0") (pin "2") (pinfunction "2_2") (pintype "passive"))
      (node (ref "R10") (pin "2") (pinfunction "2_2") (pintype "passive"))
    )
    (net (code "45") (name "Net-(LED0-Pad3)") (class "Default")
      (node (ref "LED0") (pin "3") (pinfunction "3_3") (pintype "passive"))
      (node (ref "R9") (pin "2") (pinfunction "2_2") (pintype "passive"))
    )
    (net (code "46") (name "Net-(LED0-Pad4)") (class "Default")
      (node (ref "LED0") (pin "4") (pinfunction "4_4") (pintype "passive"))
      (node (ref "R8") (pin "2") (pinfunction "2_2") (pintype "passive"))
    )
    (net (code "47") (name "Net-(LED1-Pad2)") (class "Default")
      (node (ref "LED1") (pin "2") (pinfunction "2_2") (pintype "passive"))
      (node (ref "R13") (pin "2") (pinfunction "2_2") (pintype "passive"))
    )
    (net (code "48") (name "Net-(LED1-Pad3)") (class "Default")
      (node (ref "LED1") (pin "3") (pinfunction "3_3") (pintype "passive"))
      (node (ref "R12") (pin "2") (pinfunction "2_2") (pintype "passive"))
    )
    (net (code "49") (name "Net-(LED1-Pad4)") (class "Default")
      (node (ref "LED1") (pin "4") (pinfunction "4_4") (pintype "passive"))
      (node (ref "R11") (pin "2") (pinfunction "2_2") (pintype "passive"))
    )
    (net (code "50") (name "Net-(Q1-PadB)") (class "Default")
      (node (ref "Q1") (pin "B") (pinfunction "B_B") (pintype "passive"))
      (node (ref "R3") (pin "2") (pinfunction "2_2") (pintype "passive"))
    )
    (net (code "51") (name "Net-(Q2-PadB)") (class "Default")
      (node (ref "Q2") (pin "B") (pinfunction "B_B") (pintype "passive"))
      (node (ref "R4") (pin "2") (pinfunction "2_2") (pintype "passive"))
    )
    (net (code "52") (name "Net-(U1-IO17)") (class "Default")
      (node (ref "R38") (pin "1") (pinfunction "1_1") (pintype "passive"))
      (node (ref "U1") (pin "28") (pinfunction "IO17_28") (pintype "bidirectional"))
    )
    (net (code "53") (name "Net-(U3-OE)") (class "Default")
      (node (ref "R37") (pin "2") (pinfunction "2_2") (pintype "passive"))
      (node (ref "U3") (pin "8") (pinfunction "OE_8") (pintype "input"))
    )
    (net (code "54") (name "Net-(U4-CRS_DV{slash}MODE2)") (class "Default")
      (node (ref "R24") (pin "1") (pinfunction "1_1") (pintype "passive"))
      (node (ref "R33") (pin "1") (pinfunction "1_1") (pintype "passive"))
      (node (ref "U4") (pin "11") (pinfunction "CRS_DV/MODE2_11") (pintype "bidirectional"))
    )
    (net (code "55") (name "Net-(U4-LED1{slash}REGOFF)") (class "Default")
      (node (ref "R30") (pin "1") (pinfunction "1_1") (pintype "passive"))
      (node (ref "R31") (pin "1") (pinfunction "1_1") (pintype "passive"))
      (node (ref "U4") (pin "3") (pinfunction "LED1/REGOFF_3") (pintype "bidirectional"))
    )
    (net (code "56") (name "Net-(U4-LED2{slash}~{NINTSEL})") (class "Default")
      (node (ref "R29") (pin "1") (pinfunction "1_1") (pintype "passive"))
      (node (ref "U4") (pin "2") (pinfunction "LED2/~{NINTSEL}_2") (pintype "bidirectional"))
    )
    (net (code "57") (name "Net-(U4-RBIAS)") (class "Default")
      (node (ref "R28") (pin "2") (pinfunction "2_2") (pintype "passive"))
      (node (ref "U4") (pin "24") (pinfunction "RBIAS_24") (pintype "input"))
    )
    (net (code "58") (name "Net-(U4-RXD0{slash}MODE0)") (class "Default")
      (node (ref "R26") (pin "1") (pinfunction "1_1") (pintype "passive"))
      (node (ref "R35") (pin "1") (pinfunction "1_1") (pintype "passive"))
      (node (ref "U4") (pin "8") (pinfunction "RXD0/MODE0_8") (pintype "bidirectional"))
    )
    (net (code "59") (name "Net-(U4-RXD1{slash}MODE1)") (class "Default")
      (node (ref "R25") (pin "1") (pinfunction "1_1") (pintype "passive"))
      (node (ref "R34") (pin "1") (pinfunction "1_1") (pintype "passive"))
      (node (ref "U4") (pin "7") (pinfunction "RXD1/MODE1_7") (pintype "bidirectional"))
    )
    (net (code "60") (name "Net-(U4-RXER{slash}PHYADO)") (class "Default")
      (node (ref "R32") (pin "1") (pinfunction "1_1") (pintype "passive"))
      (node (ref "U4") (pin "10") (pinfunction "RXER/PHYADO_10") (pintype "bidirectional"))
    )
    (net (code "61") (name "Net-(U4-~{NRST})") (class "Default")
      (node (ref "C11") (pin "1") (pinfunction "1_1") (pintype "passive"))
      (node (ref "R36") (pin "1") (pinfunction "1_1") (pintype "passive"))
      (node (ref "U4") (pin "15") (pinfunction "~{NRST}_15") (pintype "input"))
    )
    (net (code "62") (name "Net-(U6-~{RST})") (class "Default")
      (node (ref "R5") (pin "2") (pinfunction "2_2") (pintype "passive"))
      (node (ref "U6") (pin "9") (pinfunction "~{RST}_9") (pintype "input"))
    )
    (net (code "63") (name "Net-(U6-~{SUSPENDB})") (class "Default")
      (node (ref "R6") (pin "1") (pinfunction "1_1") (pintype "passive"))
      (node (ref "U6") (pin "11") (pinfunction "~{SUSPENDB}_11") (pintype "output"))
    )
    (net (code "64") (name "PHY_VDDCR") (class "Default")
      (node (ref "C12") (pin "1") (pinfunction "1_1") (pintype "passive"))
      (node (ref "U4") (pin "6") (pinfunction "VDDCR_6") (pintype "power_in"))
    )
    (net (code "65") (name "U0_DTR") (class "Default")
      (node (ref "Q2") (pin "E") (pinfunction "E_E") (pintype "passive"))
      (node (ref "R3") (pin "1") (pinfunction "1_1") (pintype "passive"))
      (node (ref "U6") (pin "28") (pinfunction "DTR_28") (pintype "output"))
    )
    (net (code "66") (name "U0_RTS") (class "Default")
      (node (ref "Q1") (pin "E") (pinfunction "E_E") (pintype "passive"))
      (node (ref "R4") (pin "1") (pinfunction "1_1") (pintype "passive"))
      (node (ref "U6") (pin "24") (pinfunction "RTS_24") (pintype "output"))
    )
    (net (code "67") (name "U0_RXD0") (class "Default")
      (node (ref "U1") (pin "34") (pinfunction "RXD0_34") (pintype "bidirectional"))
      (node (ref "U6") (pin "26") (pinfunction "TXD_26") (pintype "output"))
    )
    (net (code "68") (name "U0_TXD0") (class "Default")
      (node (ref "U1") (pin "35") (pinfunction "TXD0_35") (pintype "bidirectional"))
      (node (ref "U6") (pin "25") (pinfunction "RXD_25") (pintype "input"))
    )
    (net (code "69") (name "USB_DN") (class "Default")
      (node (ref "J1") (pin "3") (pinfunction "3_3") (pintype "passive"))
      (node (ref "U6") (pin "5") (pinfunction "D-_5") (pintype "bidirectional"))
    )
    (net (code "70") (name "USB_DP") (class "Default")
      (node (ref "J1") (pin "2") (pinfunction "2_2") (pintype "passive"))
      (node (ref "U6") (pin "4") (pinfunction "D+_4") (pintype "bidirectional"))
    )
    (net (code "71") (name "VDDA") (class "Default")
      (node (ref "C10") (pin "1") (pinfunction "1_1") (pintype "passive"))
      (node (ref "C13") (pin "1") (pinfunction "1_1") (pintype "passive"))
      (node (ref "C14") (pin "1") (pinfunction "1_1") (pintype "passive"))
      (node (ref "C16") (pin "2") (pinfunction "2_2") (pintype "passive"))
      (node (ref "FB1") (pin "2") (pinfunction "P$2_2") (pintype "bidirectional"))
      (node (ref "J2") (pin "L1") (pinfunction "L1_L1") (pintype "passive"))
      (node (ref "J2") (pin "L3") (pinfunction "L3_L3") (pintype "passive"))
      (node (ref "J2") (pin "R3") (pinfunction "CT_R3") (pintype "input"))
      (node (ref "R20") (pin "2") (pinfunction "2_2") (pintype "passive"))
      (node (ref "R21") (pin "2") (pinfunction "2_2") (pintype "passive"))
      (node (ref "R22") (pin "2") (pinfunction "2_2") (pintype "passive"))
      (node (ref "R23") (pin "2") (pinfunction "2_2") (pintype "passive"))
      (node (ref "R31") (pin "2") (pinfunction "2_2") (pintype "passive"))
      (node (ref "U4") (pin "1") (pinfunction "VDD2A_1") (pintype "power_in"))
      (node (ref "U4") (pin "19") (pinfunction "VDD1A_19") (pintype "power_in"))
    )
    (net (code "72") (name "V_USB") (class "Default")
      (node (ref "D1") (pin "+") (pinfunction "+_+") (pintype "passive"))
      (node (ref "J1") (pin "1") (pinfunction "1_1") (pintype "passive"))
      (node (ref "U6") (pin "8") (pinfunction "VBUS_8") (pintype "power_in"))
    )
    (net (code "73") (name "unconnected-(J1-Pad4)") (class "Default")
      (node (ref "J1") (pin "4") (pinfunction "4_4") (pintype "passive"))
    )
    (net (code "74") (name "unconnected-(J2-PadR4)") (class "Default")
      (node (ref "J2") (pin "R4") (pinfunction "R4_R4") (pintype "input"))
    )
    (net (code "75") (name "unconnected-(J2-PadR5)") (class "Default")
      (node (ref "J2") (pin "R5") (pinfunction "R5_R5") (pintype "input"))
    )
    (net (code "76") (name "unconnected-(J2-PadR6)") (class "Default")
      (node (ref "J2") (pin "R6") (pinfunction "R6_R6") (pintype "input"))
    )
    (net (code "77") (name "unconnected-(U1-SCL{slash}CLK-Pad20)") (class "Default")
      (node (ref "U1") (pin "20") (pinfunction "SCL/CLK_20") (pintype "bidirectional"))
    )
    (net (code "78") (name "unconnected-(U1-SCS{slash}CMD-Pad19)") (class "Default")
      (node (ref "U1") (pin "19") (pinfunction "SCS/CMD_19") (pintype "bidirectional"))
    )
    (net (code "79") (name "unconnected-(U1-SDI{slash}SD1-Pad22)") (class "Default")
      (node (ref "U1") (pin "22") (pinfunction "SDI/SD1_22") (pintype "bidirectional"))
    )
    (net (code "80") (name "unconnected-(U1-SDO{slash}SD0-Pad21)") (class "Default")
      (node (ref "U1") (pin "21") (pinfunction "SDO/SD0_21") (pintype "bidirectional"))
    )
    (net (code "81") (name "unconnected-(U1-SHD{slash}SD2-Pad17)") (class "Default")
      (node (ref "U1") (pin "17") (pinfunction "SHD/SD2_17") (pintype "bidirectional"))
    )
    (net (code "82") (name "unconnected-(U1-SWP{slash}SD3-Pad18)") (class "Default")
      (node (ref "U1") (pin "18") (pinfunction "SWP/SD3_18") (pintype "bidirectional"))
    )
    (net (code "83") (name "unconnected-(U3-NC-Pad6)") (class "Default")
      (node (ref "U3") (pin "6") (pinfunction "NC_6") (pintype "no_connect"))
    )
    (net (code "84") (name "unconnected-(U3-NC_2-Pad9)") (class "Default")
      (node (ref "U3") (pin "9") (pinfunction "NC_2_9") (pintype "no_connect"))
    )
    (net (code "85") (name "unconnected-(U4-XTAL2-Pad4)") (class "Default")
      (node (ref "U4") (pin "4") (pinfunction "XTAL2_4") (pintype "output"))
    )
    (net (code "86") (name "unconnected-(U4-~{NINT}{slash}REFCLKO-Pad14)") (class "Default")
      (node (ref "U4") (pin "14") (pinfunction "~{NINT}/REFCLKO_14") (pintype "output"))
    )
    (net (code "87") (name "unconnected-(U6-CHR0-Pad15)") (class "Default")
      (node (ref "U6") (pin "15") (pinfunction "CHR0_15") (pintype "output"))
    )
    (net (code "88") (name "unconnected-(U6-CHR1-Pad14)") (class "Default")
      (node (ref "U6") (pin "14") (pinfunction "CHR1_14") (pintype "output"))
    )
    (net (code "89") (name "unconnected-(U6-CHREN-Pad13)") (class "Default")
      (node (ref "U6") (pin "13") (pinfunction "CHREN_13") (pintype "output"))
    )
    (net (code "90") (name "unconnected-(U6-CTS-Pad23)") (class "Default")
      (node (ref "U6") (pin "23") (pinfunction "CTS_23") (pintype "input"))
    )
    (net (code "91") (name "unconnected-(U6-DCD-Pad1)") (class "Default")
      (node (ref "U6") (pin "1") (pinfunction "DCD_1") (pintype "input"))
    )
    (net (code "92") (name "unconnected-(U6-DSR-Pad27)") (class "Default")
      (node (ref "U6") (pin "27") (pinfunction "DSR_27") (pintype "input"))
    )
    (net (code "93") (name "unconnected-(U6-GPIO.0{slash}TXT-Pad19)") (class "Default")
      (node (ref "U6") (pin "19") (pinfunction "GPIO.0/TXT_19") (pintype "bidirectional"))
    )
    (net (code "94") (name "unconnected-(U6-GPIO.1{slash}RXT-Pad18)") (class "Default")
      (node (ref "U6") (pin "18") (pinfunction "GPIO.1/RXT_18") (pintype "bidirectional"))
    )
    (net (code "95") (name "unconnected-(U6-GPIO.2{slash}RS485-Pad17)") (class "Default")
      (node (ref "U6") (pin "17") (pinfunction "GPIO.2/RS485_17") (pintype "bidirectional"))
    )
    (net (code "96") (name "unconnected-(U6-GPIO.3{slash}WAKEUP-Pad16)") (class "Default")
      (node (ref "U6") (pin "16") (pinfunction "GPIO.3/WAKEUP_16") (pintype "bidirectional"))
    )
    (net (code "97") (name "unconnected-(U6-GPIO.4-Pad22)") (class "Default")
      (node (ref "U6") (pin "22") (pinfunction "GPIO.4_22") (pintype "bidirectional"))
    )
    (net (code "98") (name "unconnected-(U6-GPIO.5-Pad21)") (class "Default")
      (node (ref "U6") (pin "21") (pinfunction "GPIO.5_21") (pintype "bidirectional"))
    )
    (net (code "99") (name "unconnected-(U6-GPIO.6-Pad20)") (class "Default")
      (node (ref "U6") (pin "20") (pinfunction "GPIO.6_20") (pintype "bidirectional"))
    )
    (net (code "100") (name "unconnected-(U6-RI{slash}CLK-Pad2)") (class "Default")
      (node (ref "U6") (pin "2") (pinfunction "RI/CLK_2") (pintype "bidirectional"))
    )
    (net (code "101") (name "unconnected-(U6-SUSPEND-Pad12)") (class "Default")
      (node (ref "U6") (pin "12") (pinfunction "SUSPEND_12") (pintype "output"))
    )
  )
)
